# Connector.net
KiCad netlist of a schematic drawn in Altium Designer
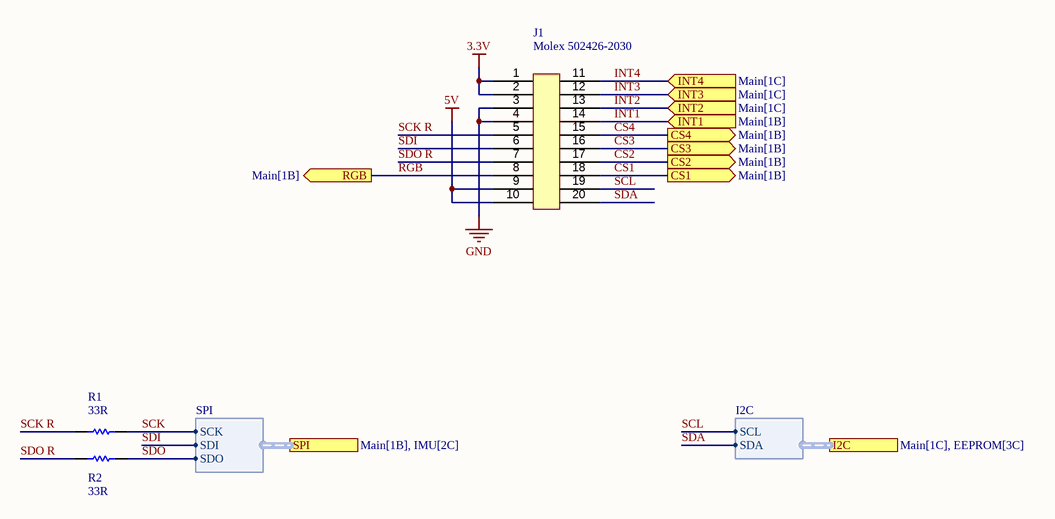
[diagram p0: Connector.SchDoc]

(export (version "E")
  (design (tool "Eeschema 10.0.6"))
  (components
    (comp (ref "J1")
      (value "Molex 502426-2030")
      (footprint "Molex 502426-2030")
      (libsource (lib "x-io") (part "Molex 502426-2030"))
    )
    (comp (ref "R1") (value "33R") (footprint "Resistor 0201") (libsource (lib "x-io") (part "Resistor")))
    (comp (ref "R2") (value "33R") (footprint "Resistor 0201") (libsource (lib "x-io") (part "Resistor")))
  )
  (nets
    (net (code "3") (name "/CS1") (class "Default")
      (node (ref "J1") (pin "18") (pinfunction "18_18") (pintype "passive"))
    )
    (net (code "4") (name "/CS2") (class "Default")
      (node (ref "J1") (pin "17") (pinfunction "17_17") (pintype "passive"))
    )
    (net (code "5") (name "/CS3") (class "Default")
      (node (ref "J1") (pin "16") (pinfunction "16_16") (pintype "passive"))
    )
    (net (code "6") (name "/CS4") (class "Default")
      (node (ref "J1") (pin "15") (pinfunction "15_15") (pintype "passive"))
    )
    (net (code "7") (name "/INT1") (class "Default")
      (node (ref "J1") (pin "14") (pinfunction "14_14") (pintype "passive"))
    )
    (net (code "8") (name "/INT2") (class "Default")
      (node (ref "J1") (pin "13") (pinfunction "13_13") (pintype "passive"))
    )
    (net (code "9") (name "/INT3") (class "Default")
      (node (ref "J1") (pin "12") (pinfunction "12_12") (pintype "passive"))
    )
    (net (code "10") (name "/INT4") (class "Default")
      (node (ref "J1") (pin "11") (pinfunction "11_11") (pintype "passive"))
    )
    (net (code "11") (name "/RGB") (class "Default")
      (node (ref "J1") (pin "8") (pinfunction "8_8") (pintype "passive"))
    )
    (net (code "12") (name "/SCK") (class "Default")
      (node (ref "R1") (pin "2") (pinfunction "2_2") (pintype "passive"))
    )
    (net (code "13") (name "/SCK R") (class "Default")
      (node (ref "J1") (pin "5") (pinfunction "5_5") (pintype "passive"))
      (node (ref "R1") (pin "1") (pinfunction "1_1") (pintype "passive"))
    )
    (net (code "14") (name "/SCL") (class "Default")
      (node (ref "J1") (pin "19") (pinfunction "19_19") (pintype "passive"))
    )
    (net (code "15") (name "/SDA") (class "Default")
      (node (ref "J1") (pin "20") (pinfunction "20_20") (pintype "passive"))
    )
    (net (code "16") (name "/SDI") (class "Default")
      (node (ref "J1") (pin "6") (pinfunction "6_6") (pintype "passive"))
    )
    (net (code "17") (name "/SDO") (class "Default")
      (node (ref "R2") (pin "2") (pinfunction "2_2") (pintype "passive"))
    )
    (net (code "18") (name "/SDO R") (class "Default")
      (node (ref "J1") (pin "7") (pinfunction "7_7") (pintype "passive"))
      (node (ref "R2") (pin "1") (pinfunction "1_1") (pintype "passive"))
    )
    (net (code "21") (name "3.3V") (class "Default")
      (node (ref "J1") (pin "1") (pinfunction "1_1") (pintype "passive"))
      (node (ref "J1") (pin "2") (pinfunction "2_2") (pintype "passive"))
    )
    (net (code "22") (name "5V") (class "Default")
      (node (ref "J1") (pin "10") (pinfunction "10_10") (pintype "passive"))
      (node (ref "J1") (pin "9") (pinfunction "9_9") (pintype "passive"))
    )
    (net (code "23") (name "GND") (class "Default")
      (node (ref "J1") (pin "3") (pinfunction "3_3") (pintype "passive"))
      (node (ref "J1") (pin "4") (pinfunction "4_4") (pintype "passive"))
    )
  )
)
